# PROB_S7CAS_DAC.net
KiCad netlist of a schematic drawn in Altium Designer
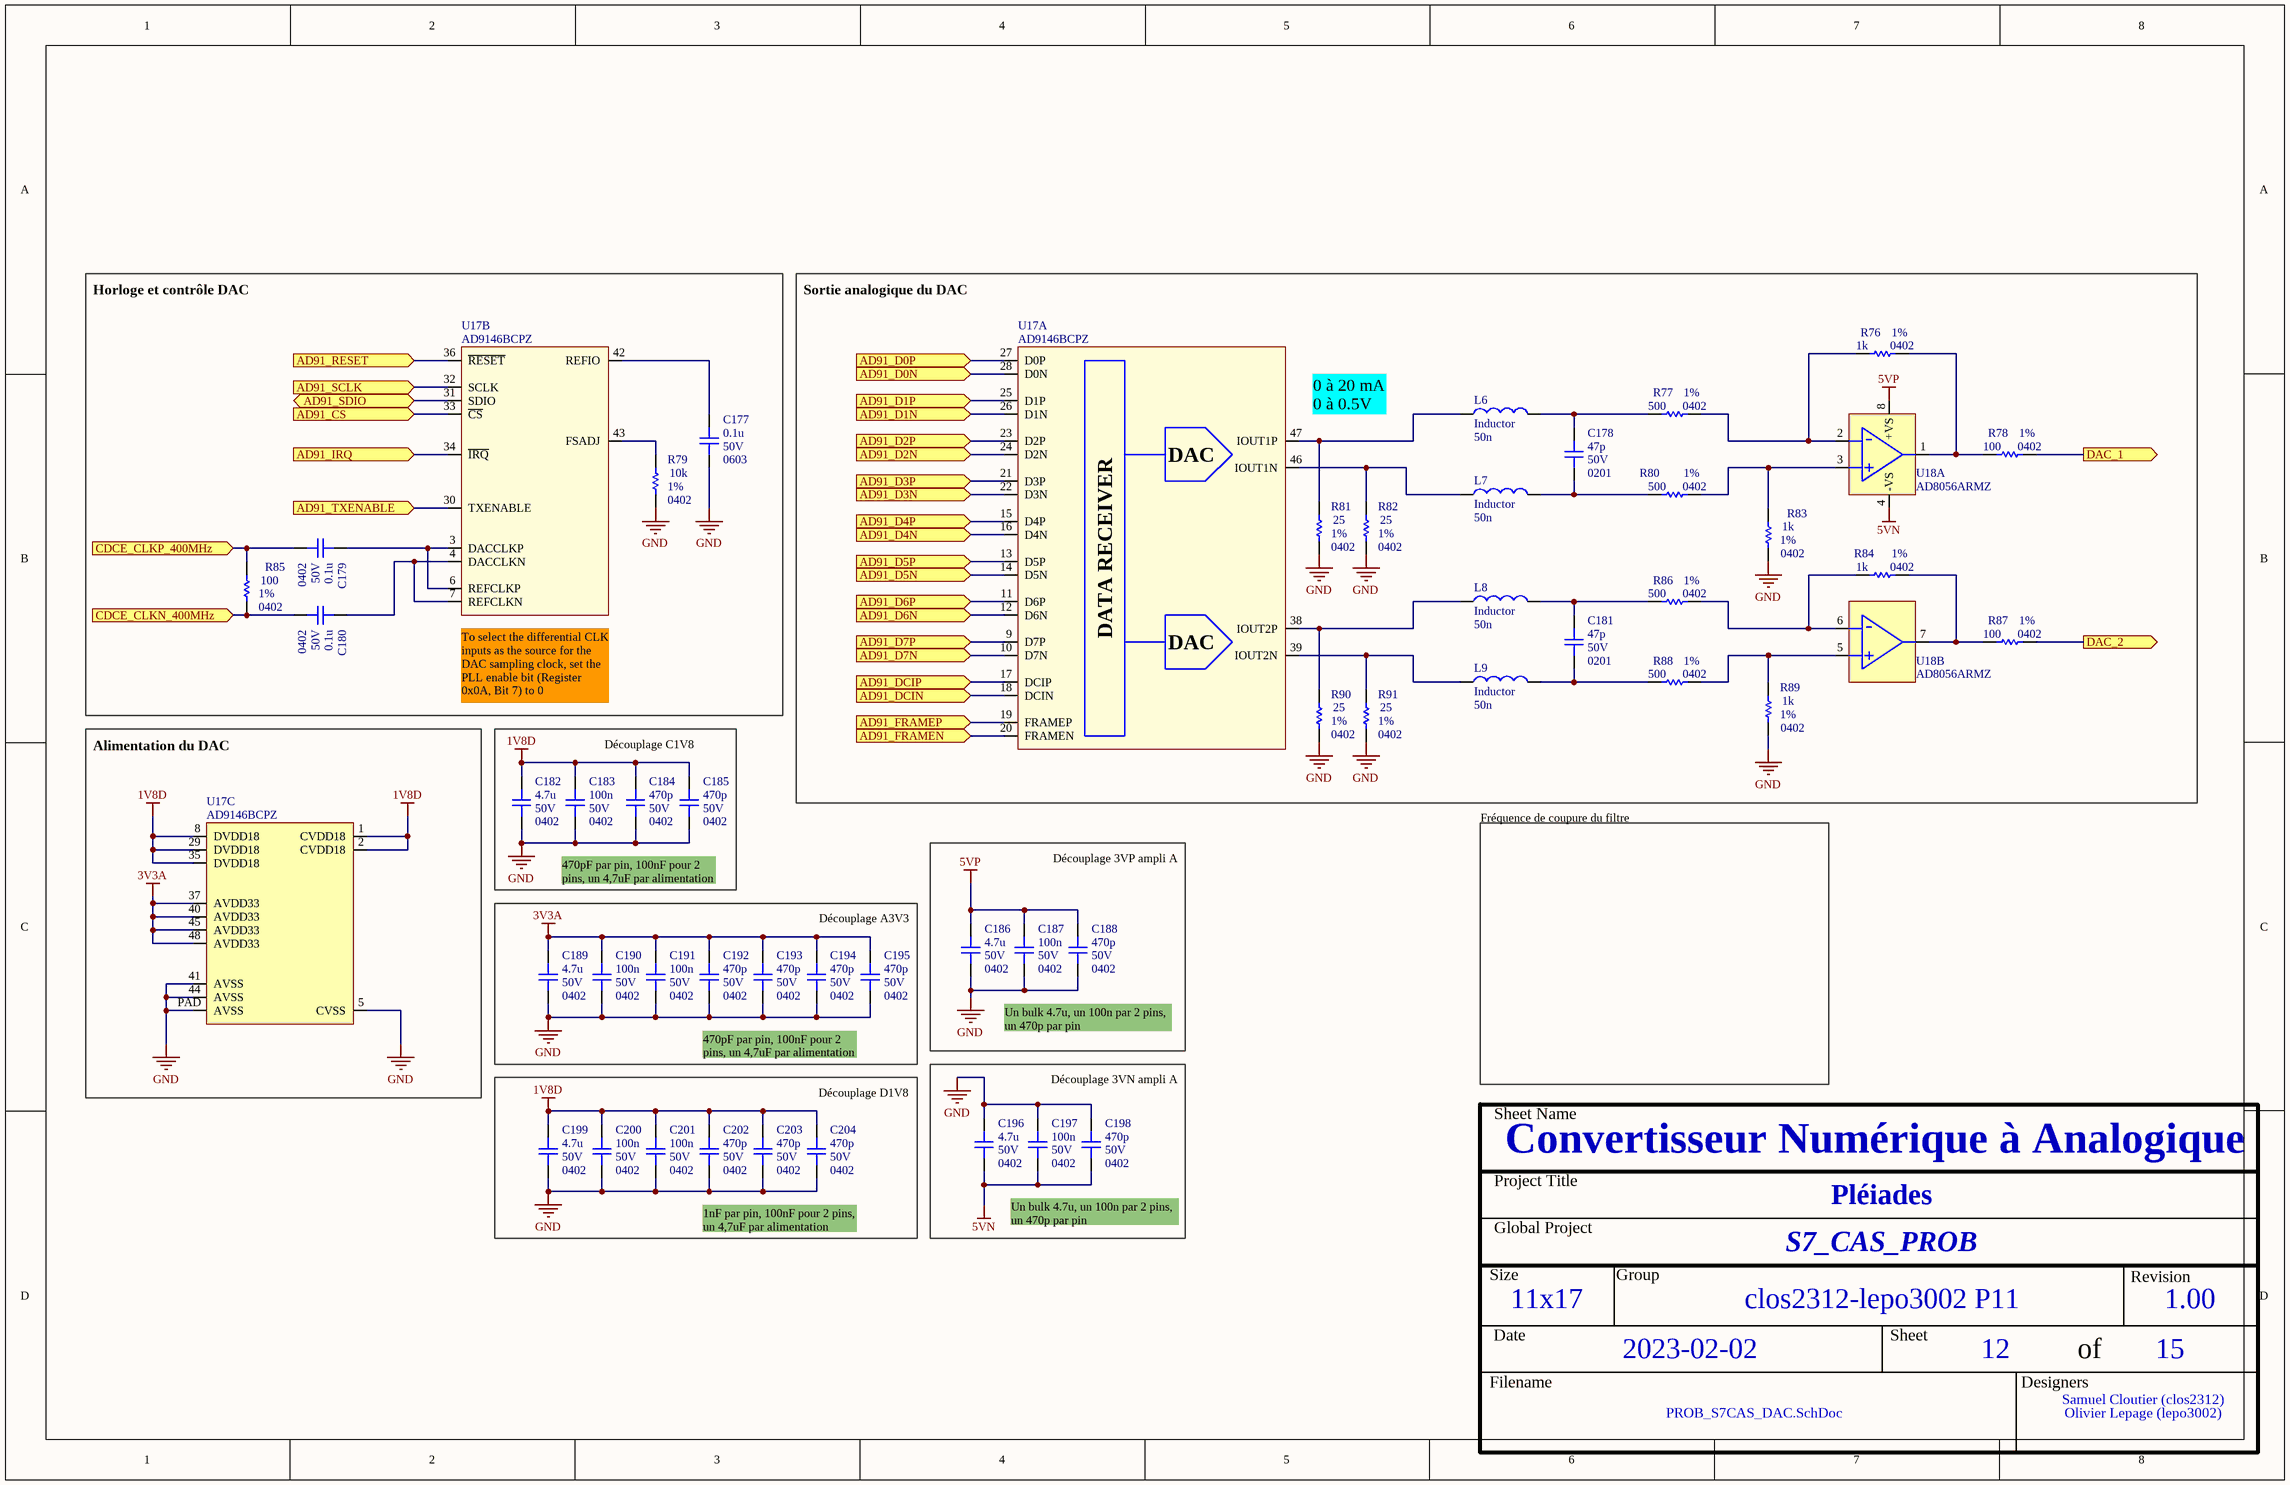
[diagram p0: PROB_S7CAS_DAC.SchDoc]

(export (version "E")
  (design (tool "Eeschema 10.0.6"))
  (components
    (comp (ref "C177")
      (value "0.1u")
      (footprint "CAP_0603")
      (description "CAP - 0603")
      (fields
        (field (name "VOLTAGE") "50V")
        (field (name "PACKAGE") "0603")
        (field (name "CREATEDBY") "Jonathan Bouchard")
      )
      (libsource (lib "S7CAS_LIB2021") (part "CAP - 0603"))
    )
    (comp (ref "C178")
      (value "47p")
      (footprint "CAP_0201")
      (description "CAP - 0201")
      (fields
        (field (name "VOLTAGE") "50V")
        (field (name "PACKAGE") "0201")
        (field (name "CREATEDBY") "Jonathan Bouchard")
      )
      (libsource (lib "S7CAS_LIB2021") (part "CAP - 0201"))
    )
    (comp (ref "C179")
      (value "0.1u")
      (footprint "CAP_0402")
      (description "CAP - 0402")
      (fields
        (field (name "VOLTAGE") "50V")
        (field (name "PACKAGE") "0402")
        (field (name "CREATEDBY") "Jonathan Bouchard")
      )
      (libsource (lib "S7CAS_LIB2021") (part "CAP - 0402"))
    )
    (comp (ref "C180")
      (value "0.1u")
      (footprint "CAP_0402")
      (description "CAP - 0402")
      (fields
        (field (name "VOLTAGE") "50V")
        (field (name "PACKAGE") "0402")
        (field (name "CREATEDBY") "Jonathan Bouchard")
      )
      (libsource (lib "S7CAS_LIB2021") (part "CAP - 0402"))
    )
    (comp (ref "C181")
      (value "47p")
      (footprint "CAP_0201")
      (description "CAP - 0201")
      (fields
        (field (name "VOLTAGE") "50V")
        (field (name "PACKAGE") "0201")
        (field (name "CREATEDBY") "Jonathan Bouchard")
      )
      (libsource (lib "S7CAS_LIB2021") (part "CAP - 0201"))
    )
    (comp (ref "C182")
      (value "4.7u")
      (footprint "CAP_0402")
      (description "CAP - 0402")
      (fields
        (field (name "VOLTAGE") "50V")
        (field (name "PACKAGE") "0402")
        (field (name "CREATEDBY") "Jonathan Bouchard")
      )
      (libsource (lib "S7CAS_LIB2021") (part "CAP - 0402"))
    )
    (comp (ref "C183")
      (value "100n")
      (footprint "CAP_0402")
      (description "CAP - 0402")
      (fields
        (field (name "VOLTAGE") "50V")
        (field (name "PACKAGE") "0402")
        (field (name "CREATEDBY") "Jonathan Bouchard")
      )
      (libsource (lib "S7CAS_LIB2021") (part "CAP - 0402"))
    )
    (comp (ref "C184")
      (value "470p")
      (footprint "CAP_0402")
      (description "CAP - 0402")
      (fields
        (field (name "VOLTAGE") "50V")
        (field (name "PACKAGE") "0402")
        (field (name "CREATEDBY") "Jonathan Bouchard")
      )
      (libsource (lib "S7CAS_LIB2021") (part "CAP - 0402"))
    )
    (comp (ref "C185")
      (value "470p")
      (footprint "CAP_0402")
      (description "CAP - 0402")
      (fields
        (field (name "VOLTAGE") "50V")
        (field (name "PACKAGE") "0402")
        (field (name "CREATEDBY") "Jonathan Bouchard")
      )
      (libsource (lib "S7CAS_LIB2021") (part "CAP - 0402"))
    )
    (comp (ref "C186")
      (value "4.7u")
      (footprint "CAP_0402")
      (description "CAP - 0402")
      (fields
        (field (name "VOLTAGE") "50V")
        (field (name "PACKAGE") "0402")
        (field (name "CREATEDBY") "Jonathan Bouchard")
      )
      (libsource (lib "S7CAS_LIB2021") (part "CAP - 0402"))
    )
    (comp (ref "C187")
      (value "100n")
      (footprint "CAP_0402")
      (description "CAP - 0402")
      (fields
        (field (name "VOLTAGE") "50V")
        (field (name "PACKAGE") "0402")
        (field (name "CREATEDBY") "Jonathan Bouchard")
      )
      (libsource (lib "S7CAS_LIB2021") (part "CAP - 0402"))
    )
    (comp (ref "C188")
      (value "470p")
      (footprint "CAP_0402")
      (description "CAP - 0402")
      (fields
        (field (name "VOLTAGE") "50V")
        (field (name "PACKAGE") "0402")
        (field (name "CREATEDBY") "Jonathan Bouchard")
      )
      (libsource (lib "S7CAS_LIB2021") (part "CAP - 0402"))
    )
    (comp (ref "C189")
      (value "4.7u")
      (footprint "CAP_0402")
      (description "CAP - 0402")
      (fields
        (field (name "VOLTAGE") "50V")
        (field (name "PACKAGE") "0402")
        (field (name "CREATEDBY") "Jonathan Bouchard")
      )
      (libsource (lib "S7CAS_LIB2021") (part "CAP - 0402"))
    )
    (comp (ref "C190")
      (value "100n")
      (footprint "CAP_0402")
      (description "CAP - 0402")
      (fields
        (field (name "VOLTAGE") "50V")
        (field (name "PACKAGE") "0402")
        (field (name "CREATEDBY") "Jonathan Bouchard")
      )
      (libsource (lib "S7CAS_LIB2021") (part "CAP - 0402"))
    )
    (comp (ref "C191")
      (value "100n")
      (footprint "CAP_0402")
      (description "CAP - 0402")
      (fields
        (field (name "VOLTAGE") "50V")
        (field (name "PACKAGE") "0402")
        (field (name "CREATEDBY") "Jonathan Bouchard")
      )
      (libsource (lib "S7CAS_LIB2021") (part "CAP - 0402"))
    )
    (comp (ref "C192")
      (value "470p")
      (footprint "CAP_0402")
      (description "CAP - 0402")
      (fields
        (field (name "VOLTAGE") "50V")
        (field (name "PACKAGE") "0402")
        (field (name "CREATEDBY") "Jonathan Bouchard")
      )
      (libsource (lib "S7CAS_LIB2021") (part "CAP - 0402"))
    )
    (comp (ref "C193")
      (value "470p")
      (footprint "CAP_0402")
      (description "CAP - 0402")
      (fields
        (field (name "VOLTAGE") "50V")
        (field (name "PACKAGE") "0402")
        (field (name "CREATEDBY") "Jonathan Bouchard")
      )
      (libsource (lib "S7CAS_LIB2021") (part "CAP - 0402"))
    )
    (comp (ref "C194")
      (value "470p")
      (footprint "CAP_0402")
      (description "CAP - 0402")
      (fields
        (field (name "VOLTAGE") "50V")
        (field (name "PACKAGE") "0402")
        (field (name "CREATEDBY") "Jonathan Bouchard")
      )
      (libsource (lib "S7CAS_LIB2021") (part "CAP - 0402"))
    )
    (comp (ref "C195")
      (value "470p")
      (footprint "CAP_0402")
      (description "CAP - 0402")
      (fields
        (field (name "VOLTAGE") "50V")
        (field (name "PACKAGE") "0402")
        (field (name "CREATEDBY") "Jonathan Bouchard")
      )
      (libsource (lib "S7CAS_LIB2021") (part "CAP - 0402"))
    )
    (comp (ref "C196")
      (value "4.7u")
      (footprint "CAP_0402")
      (description "CAP - 0402")
      (fields
        (field (name "VOLTAGE") "50V")
        (field (name "PACKAGE") "0402")
        (field (name "CREATEDBY") "Jonathan Bouchard")
      )
      (libsource (lib "S7CAS_LIB2021") (part "CAP - 0402"))
    )
    (comp (ref "C197")
      (value "100n")
      (footprint "CAP_0402")
      (description "CAP - 0402")
      (fields
        (field (name "VOLTAGE") "50V")
        (field (name "PACKAGE") "0402")
        (field (name "CREATEDBY") "Jonathan Bouchard")
      )
      (libsource (lib "S7CAS_LIB2021") (part "CAP - 0402"))
    )
    (comp (ref "C198")
      (value "470p")
      (footprint "CAP_0402")
      (description "CAP - 0402")
      (fields
        (field (name "VOLTAGE") "50V")
        (field (name "PACKAGE") "0402")
        (field (name "CREATEDBY") "Jonathan Bouchard")
      )
      (libsource (lib "S7CAS_LIB2021") (part "CAP - 0402"))
    )
    (comp (ref "C199")
      (value "4.7u")
      (footprint "CAP_0402")
      (description "CAP - 0402")
      (fields
        (field (name "VOLTAGE") "50V")
        (field (name "PACKAGE") "0402")
        (field (name "CREATEDBY") "Jonathan Bouchard")
      )
      (libsource (lib "S7CAS_LIB2021") (part "CAP - 0402"))
    )
    (comp (ref "C200")
      (value "100n")
      (footprint "CAP_0402")
      (description "CAP - 0402")
      (fields
        (field (name "VOLTAGE") "50V")
        (field (name "PACKAGE") "0402")
        (field (name "CREATEDBY") "Jonathan Bouchard")
      )
      (libsource (lib "S7CAS_LIB2021") (part "CAP - 0402"))
    )
    (comp (ref "C201")
      (value "100n")
      (footprint "CAP_0402")
      (description "CAP - 0402")
      (fields
        (field (name "VOLTAGE") "50V")
        (field (name "PACKAGE") "0402")
        (field (name "CREATEDBY") "Jonathan Bouchard")
      )
      (libsource (lib "S7CAS_LIB2021") (part "CAP - 0402"))
    )
    (comp (ref "C202")
      (value "470p")
      (footprint "CAP_0402")
      (description "CAP - 0402")
      (fields
        (field (name "VOLTAGE") "50V")
        (field (name "PACKAGE") "0402")
        (field (name "CREATEDBY") "Jonathan Bouchard")
      )
      (libsource (lib "S7CAS_LIB2021") (part "CAP - 0402"))
    )
    (comp (ref "C203")
      (value "470p")
      (footprint "CAP_0402")
      (description "CAP - 0402")
      (fields
        (field (name "VOLTAGE") "50V")
        (field (name "PACKAGE") "0402")
        (field (name "CREATEDBY") "Jonathan Bouchard")
      )
      (libsource (lib "S7CAS_LIB2021") (part "CAP - 0402"))
    )
    (comp (ref "C204")
      (value "470p")
      (footprint "CAP_0402")
      (description "CAP - 0402")
      (fields
        (field (name "VOLTAGE") "50V")
        (field (name "PACKAGE") "0402")
        (field (name "CREATEDBY") "Jonathan Bouchard")
      )
      (libsource (lib "S7CAS_LIB2021") (part "CAP - 0402"))
    )
    (comp (ref "L6")
      (value "Inductor")
      (footprint "INDM5250X66N")
      (description "IND PWR BEAD 50NH 48A SMD")
      (fields (field (name "ALTIUM_VALUE") "50n"))
      (libsource (lib "LIB_TEMP_S7CAS_SCH") (part "Inductor"))
    )
    (comp (ref "L7")
      (value "Inductor")
      (footprint "INDM5250X66N")
      (description "IND PWR BEAD 50NH 48A SMD")
      (fields (field (name "ALTIUM_VALUE") "50n"))
      (libsource (lib "LIB_TEMP_S7CAS_SCH") (part "Inductor"))
    )
    (comp (ref "L8")
      (value "Inductor")
      (footprint "INDM5250X66N")
      (description "IND PWR BEAD 50NH 48A SMD")
      (fields (field (name "ALTIUM_VALUE") "50n"))
      (libsource (lib "LIB_TEMP_S7CAS_SCH") (part "Inductor"))
    )
    (comp (ref "L9")
      (value "Inductor")
      (footprint "INDM5250X66N")
      (description "IND PWR BEAD 50NH 48A SMD")
      (fields (field (name "ALTIUM_VALUE") "50n"))
      (libsource (lib "LIB_TEMP_S7CAS_SCH") (part "Inductor"))
    )
    (comp (ref "R76")
      (value "1k")
      (footprint "RES_0402")
      (description "RES - 0402")
      (fields
        (field (name "VOLTAGE") "50V")
        (field (name "POWER") "1/16W")
        (field (name "PACKAGE") "0402")
        (field (name "PRECISION") "1%")
        (field (name "CREATEDBY") "Jonathan Bouchard")
      )
      (libsource (lib "S7CAS_LIB2021") (part "RES - 0402"))
    )
    (comp (ref "R77")
      (value "500")
      (footprint "RES_0402")
      (description "RES - 0402")
      (fields
        (field (name "VOLTAGE") "50V")
        (field (name "POWER") "1/16W")
        (field (name "PACKAGE") "0402")
        (field (name "PRECISION") "1%")
        (field (name "CREATEDBY") "Jonathan Bouchard")
      )
      (libsource (lib "S7CAS_LIB2021") (part "RES - 0402"))
    )
    (comp (ref "R78")
      (value "100")
      (footprint "RES_0402")
      (description "RES - 0402")
      (fields
        (field (name "VOLTAGE") "50V")
        (field (name "POWER") "1/16W")
        (field (name "PACKAGE") "0402")
        (field (name "PRECISION") "1%")
        (field (name "CREATEDBY") "Jonathan Bouchard")
      )
      (libsource (lib "S7CAS_LIB2021") (part "RES - 0402"))
    )
    (comp (ref "R79")
      (value "10k")
      (footprint "RES_0402")
      (description "RES - 0402")
      (fields
        (field (name "VOLTAGE") "50V")
        (field (name "POWER") "1/16W")
        (field (name "PACKAGE") "0402")
        (field (name "PRECISION") "1%")
        (field (name "CREATEDBY") "Jonathan Bouchard")
      )
      (libsource (lib "S7CAS_LIB2021") (part "RES - 0402"))
    )
    (comp (ref "R80")
      (value "500")
      (footprint "RES_0402")
      (description "RES - 0402")
      (fields
        (field (name "VOLTAGE") "50V")
        (field (name "POWER") "1/16W")
        (field (name "PACKAGE") "0402")
        (field (name "PRECISION") "1%")
        (field (name "CREATEDBY") "Jonathan Bouchard")
      )
      (libsource (lib "S7CAS_LIB2021") (part "RES - 0402"))
    )
    (comp (ref "R81")
      (value "25")
      (footprint "RES_0402")
      (description "RES - 0402")
      (fields
        (field (name "VOLTAGE") "50V")
        (field (name "POWER") "1/16W")
        (field (name "PACKAGE") "0402")
        (field (name "PRECISION") "1%")
        (field (name "CREATEDBY") "Jonathan Bouchard")
      )
      (libsource (lib "S7CAS_LIB2021") (part "RES - 0402"))
    )
    (comp (ref "R82")
      (value "25")
      (footprint "RES_0402")
      (description "RES - 0402")
      (fields
        (field (name "VOLTAGE") "50V")
        (field (name "POWER") "1/16W")
        (field (name "PACKAGE") "0402")
        (field (name "PRECISION") "1%")
        (field (name "CREATEDBY") "Jonathan Bouchard")
      )
      (libsource (lib "S7CAS_LIB2021") (part "RES - 0402"))
    )
    (comp (ref "R83")
      (value "1k")
      (footprint "RES_0402")
      (description "RES - 0402")
      (fields
        (field (name "VOLTAGE") "50V")
        (field (name "POWER") "1/16W")
        (field (name "PACKAGE") "0402")
        (field (name "PRECISION") "1%")
        (field (name "CREATEDBY") "Jonathan Bouchard")
      )
      (libsource (lib "S7CAS_LIB2021") (part "RES - 0402"))
    )
    (comp (ref "R84")
      (value "1k")
      (footprint "RES_0402")
      (description "RES - 0402")
      (fields
        (field (name "VOLTAGE") "50V")
        (field (name "POWER") "1/16W")
        (field (name "PACKAGE") "0402")
        (field (name "PRECISION") "1%")
        (field (name "CREATEDBY") "Jonathan Bouchard")
      )
      (libsource (lib "S7CAS_LIB2021") (part "RES - 0402"))
    )
    (comp (ref "R85")
      (value "100")
      (footprint "RES_0402")
      (description "RES - 0402")
      (fields
        (field (name "VOLTAGE") "50V")
        (field (name "POWER") "1/16W")
        (field (name "PACKAGE") "0402")
        (field (name "PRECISION") "1%")
        (field (name "CREATEDBY") "Jonathan Bouchard")
      )
      (libsource (lib "S7CAS_LIB2021") (part "RES - 0402"))
    )
    (comp (ref "R86")
      (value "500")
      (footprint "RES_0402")
      (description "RES - 0402")
      (fields
        (field (name "VOLTAGE") "50V")
        (field (name "POWER") "1/16W")
        (field (name "PACKAGE") "0402")
        (field (name "PRECISION") "1%")
        (field (name "CREATEDBY") "Jonathan Bouchard")
      )
      (libsource (lib "S7CAS_LIB2021") (part "RES - 0402"))
    )
    (comp (ref "R87")
      (value "100")
      (footprint "RES_0402")
      (description "RES - 0402")
      (fields
        (field (name "VOLTAGE") "50V")
        (field (name "POWER") "1/16W")
        (field (name "PACKAGE") "0402")
        (field (name "PRECISION") "1%")
        (field (name "CREATEDBY") "Jonathan Bouchard")
      )
      (libsource (lib "S7CAS_LIB2021") (part "RES - 0402"))
    )
    (comp (ref "R88")
      (value "500")
      (footprint "RES_0402")
      (description "RES - 0402")
      (fields
        (field (name "VOLTAGE") "50V")
        (field (name "POWER") "1/16W")
        (field (name "PACKAGE") "0402")
        (field (name "PRECISION") "1%")
        (field (name "CREATEDBY") "Jonathan Bouchard")
      )
      (libsource (lib "S7CAS_LIB2021") (part "RES - 0402"))
    )
    (comp (ref "R89")
      (value "1k")
      (footprint "RES_0402")
      (description "RES - 0402")
      (fields
        (field (name "VOLTAGE") "50V")
        (field (name "POWER") "1/16W")
        (field (name "PACKAGE") "0402")
        (field (name "PRECISION") "1%")
        (field (name "CREATEDBY") "Jonathan Bouchard")
      )
      (libsource (lib "S7CAS_LIB2021") (part "RES - 0402"))
    )
    (comp (ref "R90")
      (value "25")
      (footprint "RES_0402")
      (description "RES - 0402")
      (fields
        (field (name "VOLTAGE") "50V")
        (field (name "POWER") "1/16W")
        (field (name "PACKAGE") "0402")
        (field (name "PRECISION") "1%")
        (field (name "CREATEDBY") "Jonathan Bouchard")
      )
      (libsource (lib "S7CAS_LIB2021") (part "RES - 0402"))
    )
    (comp (ref "R91")
      (value "25")
      (footprint "RES_0402")
      (description "RES - 0402")
      (fields
        (field (name "VOLTAGE") "50V")
        (field (name "POWER") "1/16W")
        (field (name "PACKAGE") "0402")
        (field (name "PRECISION") "1%")
        (field (name "CREATEDBY") "Jonathan Bouchard")
      )
      (libsource (lib "S7CAS_LIB2021") (part "RES - 0402"))
    )
    (comp (ref "U17")
      (value "AD9146BCPZ")
      (footprint "DAC_AD9146BCPZ")
      (description "DAC - 16BIT SRL HIGH SPEED - QFN-48")
      (fields
        (field (name "VOLTAGE") "3.13 V ~ 3.47 V / 1.71 V ~ 1.89 V")
        (field (name "MFG") "Analog Devices Inc.")
        (field (name "CREATEDBY") "Jonathan Bouchard")
      )
      (libsource (lib "S7CAS_LIB2021") (part "DAC_AD9146BCPZ"))
    )
    (comp (ref "U18")
      (value "AD8056ARMZ")
      (footprint "OPAMP_AD8056ARMZ")
      (description "OPAMP - VFB 300MHZ - 8MSOP")
      (fields
        (field (name "VOLTAGE") "8 V ~ 12 V, ±4 V ~ 6 V")
        (field (name "MFG") "Analog Devices")
        (field (name "CREATEDBY") "Jonathan Bouchard")
      )
      (libsource (lib "S7CAS_LIB2021") (part "OPAMP_AD8056ARMZ"))
    )
  )
  (nets
    (net (code "1") (name "/AD91_CS") (class "Default")
      (node (ref "U17") (pin "33") (pinfunction "~{CS}_33") (pintype "passive"))
    )
    (net (code "2") (name "/AD91_D0N") (class "Default")
      (node (ref "U17") (pin "28") (pinfunction "D0N_28") (pintype "passive"))
    )
    (net (code "3") (name "/AD91_D0P") (class "Default")
      (node (ref "U17") (pin "27") (pinfunction "D0P_27") (pintype "passive"))
    )
    (net (code "4") (name "/AD91_D1N") (class "Default")
      (node (ref "U17") (pin "26") (pinfunction "D1N_26") (pintype "passive"))
    )
    (net (code "5") (name "/AD91_D1P") (class "Default")
      (node (ref "U17") (pin "25") (pinfunction "D1P_25") (pintype "passive"))
    )
    (net (code "6") (name "/AD91_D2N") (class "Default")
      (node (ref "U17") (pin "24") (pinfunction "D2N_24") (pintype "passive"))
    )
    (net (code "7") (name "/AD91_D2P") (class "Default")
      (node (ref "U17") (pin "23") (pinfunction "D2P_23") (pintype "passive"))
    )
    (net (code "8") (name "/AD91_D3N") (class "Default")
      (node (ref "U17") (pin "22") (pinfunction "D3N_22") (pintype "passive"))
    )
    (net (code "9") (name "/AD91_D3P") (class "Default")
      (node (ref "U17") (pin "21") (pinfunction "D3P_21") (pintype "passive"))
    )
    (net (code "10") (name "/AD91_D4N") (class "Default")
      (node (ref "U17") (pin "16") (pinfunction "D4N_16") (pintype "passive"))
    )
    (net (code "11") (name "/AD91_D4P") (class "Default")
      (node (ref "U17") (pin "15") (pinfunction "D4P_15") (pintype "passive"))
    )
    (net (code "12") (name "/AD91_D5N") (class "Default")
      (node (ref "U17") (pin "14") (pinfunction "D5N_14") (pintype "passive"))
    )
    (net (code "13") (name "/AD91_D5P") (class "Default")
      (node (ref "U17") (pin "13") (pinfunction "D5P_13") (pintype "passive"))
    )
    (net (code "14") (name "/AD91_D6N") (class "Default")
      (node (ref "U17") (pin "12") (pinfunction "D6N_12") (pintype "passive"))
    )
    (net (code "15") (name "/AD91_D6P") (class "Default")
      (node (ref "U17") (pin "11") (pinfunction "D6P_11") (pintype "passive"))
    )
    (net (code "16") (name "/AD91_D7N") (class "Default")
      (node (ref "U17") (pin "10") (pinfunction "D7N_10") (pintype "passive"))
    )
    (net (code "17") (name "/AD91_D7P") (class "Default")
      (node (ref "U17") (pin "9") (pinfunction "D7P_9") (pintype "passive"))
    )
    (net (code "18") (name "/AD91_DCIN") (class "Default")
      (node (ref "U17") (pin "18") (pinfunction "DCIN_18") (pintype "passive"))
    )
    (net (code "19") (name "/AD91_DCIP") (class "Default")
      (node (ref "U17") (pin "17") (pinfunction "DCIP_17") (pintype "passive"))
    )
    (net (code "20") (name "/AD91_FRAMEN") (class "Default")
      (node (ref "U17") (pin "20") (pinfunction "FRAMEN_20") (pintype "passive"))
    )
    (net (code "21") (name "/AD91_FRAMEP") (class "Default")
      (node (ref "U17") (pin "19") (pinfunction "FRAMEP_19") (pintype "passive"))
    )
    (net (code "22") (name "/AD91_IRQ") (class "Default")
      (node (ref "U17") (pin "34") (pinfunction "~{IRQ}_34") (pintype "passive"))
    )
    (net (code "23") (name "/AD91_RESET") (class "Default")
      (node (ref "U17") (pin "36") (pinfunction "~{RESET}_36") (pintype "passive"))
    )
    (net (code "24") (name "/AD91_SCLK") (class "Default")
      (node (ref "U17") (pin "32") (pinfunction "SCLK_32") (pintype "passive"))
    )
    (net (code "25") (name "/AD91_SDIO") (class "Default")
      (node (ref "U17") (pin "31") (pinfunction "SDIO_31") (pintype "passive"))
    )
    (net (code "26") (name "/AD91_TXENABLE") (class "Default")
      (node (ref "U17") (pin "30") (pinfunction "TXENABLE_30") (pintype "passive"))
    )
    (net (code "27") (name "/CDCE_CLKN_400MHz") (class "Default")
      (node (ref "C180") (pin "1") (pinfunction "1_1") (pintype "passive"))
      (node (ref "R85") (pin "1") (pinfunction "1_1") (pintype "passive"))
    )
    (net (code "28") (name "/CDCE_CLKP_400MHz") (class "Default")
      (node (ref "C179") (pin "1") (pinfunction "1_1") (pintype "passive"))
      (node (ref "R85") (pin "2") (pinfunction "2_2") (pintype "passive"))
    )
    (net (code "29") (name "/DAC_1") (class "Default")
      (node (ref "R78") (pin "2") (pinfunction "2_2") (pintype "passive"))
    )
    (net (code "30") (name "/DAC_2") (class "Default")
      (node (ref "R87") (pin "2") (pinfunction "2_2") (pintype "passive"))
    )
    (net (code "31") (name "1V8D") (class "Default")
      (node (ref "C182") (pin "2") (pinfunction "2_2") (pintype "passive"))
      (node (ref "C183") (pin "2") (pinfunction "2_2") (pintype "passive"))
      (node (ref "C184") (pin "2") (pinfunction "2_2") (pintype "passive"))
      (node (ref "C185") (pin "2") (pinfunction "2_2") (pintype "passive"))
      (node (ref "C199") (pin "2") (pinfunction "2_2") (pintype "passive"))
      (node (ref "C200") (pin "2") (pinfunction "2_2") (pintype "passive"))
      (node (ref "C201") (pin "2") (pinfunction "2_2") (pintype "passive"))
      (node (ref "C202") (pin "2") (pinfunction "2_2") (pintype "passive"))
      (node (ref "C203") (pin "2") (pinfunction "2_2") (pintype "passive"))
      (node (ref "C204") (pin "2") (pinfunction "2_2") (pintype "passive"))
      (node (ref "U17") (pin "1") (pinfunction "CVDD18_1") (pintype "passive"))
      (node (ref "U17") (pin "2") (pinfunction "CVDD18_2") (pintype "passive"))
      (node (ref "U17") (pin "29") (pinfunction "DVDD18_29") (pintype "passive"))
      (node (ref "U17") (pin "35") (pinfunction "DVDD18_35") (pintype "passive"))
      (node (ref "U17") (pin "8") (pinfunction "DVDD18_8") (pintype "passive"))
    )
    (net (code "32") (name "3V3A") (class "Default")
      (node (ref "C189") (pin "2") (pinfunction "2_2") (pintype "passive"))
      (node (ref "C190") (pin "2") (pinfunction "2_2") (pintype "passive"))
      (node (ref "C191") (pin "2") (pinfunction "2_2") (pintype "passive"))
      (node (ref "C192") (pin "2") (pinfunction "2_2") (pintype "passive"))
      (node (ref "C193") (pin "2") (pinfunction "2_2") (pintype "passive"))
      (node (ref "C194") (pin "2") (pinfunction "2_2") (pintype "passive"))
      (node (ref "C195") (pin "2") (pinfunction "2_2") (pintype "passive"))
      (node (ref "U17") (pin "37") (pinfunction "AVDD33_37") (pintype "passive"))
      (node (ref "U17") (pin "40") (pinfunction "AVDD33_40") (pintype "passive"))
      (node (ref "U17") (pin "45") (pinfunction "AVDD33_45") (pintype "passive"))
      (node (ref "U17") (pin "48") (pinfunction "AVDD33_48") (pintype "passive"))
    )
    (net (code "33") (name "5VN") (class "Default")
      (node (ref "C196") (pin "1") (pinfunction "1_1") (pintype "passive"))
      (node (ref "C197") (pin "1") (pinfunction "1_1") (pintype "passive"))
      (node (ref "C198") (pin "1") (pinfunction "1_1") (pintype "passive"))
      (node (ref "U18") (pin "4") (pinfunction "-VS_4") (pintype "passive"))
    )
    (net (code "34") (name "5VP") (class "Default")
      (node (ref "C186") (pin "2") (pinfunction "2_2") (pintype "passive"))
      (node (ref "C187") (pin "2") (pinfunction "2_2") (pintype "passive"))
      (node (ref "C188") (pin "2") (pinfunction "2_2") (pintype "passive"))
      (node (ref "U18") (pin "8") (pinfunction "+VS_8") (pintype "passive"))
    )
    (net (code "35") (name "GND") (class "Default")
      (node (ref "C177") (pin "1") (pinfunction "1_1") (pintype "passive"))
      (node (ref "C182") (pin "1") (pinfunction "1_1") (pintype "passive"))
      (node (ref "C183") (pin "1") (pinfunction "1_1") (pintype "passive"))
      (node (ref "C184") (pin "1") (pinfunction "1_1") (pintype "passive"))
      (node (ref "C185") (pin "1") (pinfunction "1_1") (pintype "passive"))
      (node (ref "C186") (pin "1") (pinfunction "1_1") (pintype "passive"))
      (node (ref "C187") (pin "1") (pinfunction "1_1") (pintype "passive"))
      (node (ref "C188") (pin "1") (pinfunction "1_1") (pintype "passive"))
      (node (ref "C189") (pin "1") (pinfunction "1_1") (pintype "passive"))
      (node (ref "C190") (pin "1") (pinfunction "1_1") (pintype "passive"))
      (node (ref "C191") (pin "1") (pinfunction "1_1") (pintype "passive"))
      (node (ref "C192") (pin "1") (pinfunction "1_1") (pintype "passive"))
      (node (ref "C193") (pin "1") (pinfunction "1_1") (pintype "passive"))
      (node (ref "C194") (pin "1") (pinfunction "1_1") (pintype "passive"))
      (node (ref "C195") (pin "1") (pinfunction "1_1") (pintype "passive"))
      (node (ref "C196") (pin "2") (pinfunction "2_2") (pintype "passive"))
      (node (ref "C197") (pin "2") (pinfunction "2_2") (pintype "passive"))
      (node (ref "C198") (pin "2") (pinfunction "2_2") (pintype "passive"))
      (node (ref "C199") (pin "1") (pinfunction "1_1") (pintype "passive"))
      (node (ref "C200") (pin "1") (pinfunction "1_1") (pintype "passive"))
      (node (ref "C201") (pin "1") (pinfunction "1_1") (pintype "passive"))
      (node (ref "C202") (pin "1") (pinfunction "1_1") (pintype "passive"))
      (node (ref "C203") (pin "1") (pinfunction "1_1") (pintype "passive"))
      (node (ref "C204") (pin "1") (pinfunction "1_1") (pintype "passive"))
      (node (ref "R79") (pin "1") (pinfunction "1_1") (pintype "passive"))
      (node (ref "R81") (pin "1") (pinfunction "1_1") (pintype "passive"))
      (node (ref "R82") (pin "1") (pinfunction "1_1") (pintype "passive"))
      (node (ref "R83") (pin "1") (pinfunction "1_1") (pintype "passive"))
      (node (ref "R89") (pin "1") (pinfunction "1_1") (pintype "passive"))
      (node (ref "R90") (pin "1") (pinfunction "1_1") (pintype "passive"))
      (node (ref "R91") (pin "1") (pinfunction "1_1") (pintype "passive"))
      (node (ref "U17") (pin "41") (pinfunction "AVSS_41") (pintype "passive"))
      (node (ref "U17") (pin "44") (pinfunction "AVSS_44") (pintype "passive"))
      (node (ref "U17") (pin "5") (pinfunction "CVSS_5") (pintype "passive"))
      (node (ref "U17") (pin "PAD") (pinfunction "AVSS_PAD") (pintype "passive"))
    )
    (net (code "36") (name "Net-(C178-Pad1)") (class "Default")
      (node (ref "C178") (pin "1") (pinfunction "1_1") (pintype "passive"))
      (node (ref "L7") (pin "2") (pinfunction "2_2") (pintype "passive"))
      (node (ref "R80") (pin "1") (pinfunction "1_1") (pintype "passive"))
    )
    (net (code "37") (name "Net-(C178-Pad2)") (class "Default")
      (node (ref "C178") (pin "2") (pinfunction "2_2") (pintype "passive"))
      (node (ref "L6") (pin "2") (pinfunction "2_2") (pintype "passive"))
      (node (ref "R77") (pin "1") (pinfunction "1_1") (pintype "passive"))
    )
    (net (code "38") (name "Net-(C181-Pad1)") (class "Default")
      (node (ref "C181") (pin "1") (pinfunction "1_1") (pintype "passive"))
      (node (ref "L9") (pin "2") (pinfunction "2_2") (pintype "passive"))
      (node (ref "R88") (pin "1") (pinfunction "1_1") (pintype "passive"))
    )
    (net (code "39") (name "Net-(C181-Pad2)") (class "Default")
      (node (ref "C181") (pin "2") (pinfunction "2_2") (pintype "passive"))
      (node (ref "L8") (pin "2") (pinfunction "2_2") (pintype "passive"))
      (node (ref "R86") (pin "1") (pinfunction "1_1") (pintype "passive"))
    )
    (net (code "40") (name "Net-(U17A-IOUT1N)") (class "Default")
      (node (ref "L7") (pin "1") (pinfunction "1_1") (pintype "passive"))
      (node (ref "R82") (pin "2") (pinfunction "2_2") (pintype "passive"))
      (node (ref "U17") (pin "46") (pinfunction "IOUT1N_46") (pintype "passive"))
    )
    (net (code "41") (name "Net-(U17A-IOUT1P)") (class "Default")
      (node (ref "L6") (pin "1") (pinfunction "1_1") (pintype "passive"))
      (node (ref "R81") (pin "2") (pinfunction "2_2") (pintype "passive"))
      (node (ref "U17") (pin "47") (pinfunction "IOUT1P_47") (pintype "passive"))
    )
    (net (code "42") (name "Net-(U17A-IOUT2N)") (class "Default")
      (node (ref "L9") (pin "1") (pinfunction "1_1") (pintype "passive"))
      (node (ref "R91") (pin "2") (pinfunction "2_2") (pintype "passive"))
      (node (ref "U17") (pin "39") (pinfunction "IOUT2N_39") (pintype "passive"))
    )
    (net (code "43") (name "Net-(U17A-IOUT2P)") (class "Default")
      (node (ref "L8") (pin "1") (pinfunction "1_1") (pintype "passive"))
      (node (ref "R90") (pin "2") (pinfunction "2_2") (pintype "passive"))
      (node (ref "U17") (pin "38") (pinfunction "IOUT2P_38") (pintype "passive"))
    )
    (net (code "44") (name "Net-(U17B-DACCLKN)") (class "Default")
      (node (ref "C180") (pin "2") (pinfunction "2_2") (pintype "passive"))
      (node (ref "U17") (pin "4") (pinfunction "DACCLKN_4") (pintype "passive"))
      (node (ref "U17") (pin "7") (pinfunction "REFCLKN_7") (pintype "passive"))
    )
    (net (code "45") (name "Net-(U17B-DACCLKP)") (class "Default")
      (node (ref "C179") (pin "2") (pinfunction "2_2") (pintype "passive"))
      (node (ref "U17") (pin "3") (pinfunction "DACCLKP_3") (pintype "passive"))
      (node (ref "U17") (pin "6") (pinfunction "REFCLKP_6") (pintype "passive"))
    )
    (net (code "46") (name "Net-(U17B-FSADJ)") (class "Default")
      (node (ref "R79") (pin "2") (pinfunction "2_2") (pintype "passive"))
      (node (ref "U17") (pin "43") (pinfunction "FSADJ_43") (pintype "passive"))
    )
    (net (code "47") (name "Net-(U17B-REFIO)") (class "Default")
      (node (ref "C177") (pin "2") (pinfunction "2_2") (pintype "passive"))
      (node (ref "U17") (pin "42") (pinfunction "REFIO_42") (pintype "passive"))
    )
    (net (code "48") (name "Net-(U18A-+IN1)") (class "Default")
      (node (ref "R80") (pin "2") (pinfunction "2_2") (pintype "passive"))
      (node (ref "R83") (pin "2") (pinfunction "2_2") (pintype "passive"))
      (node (ref "U18") (pin "3") (pinfunction "+IN1_3") (pintype "passive"))
    )
    (net (code "49") (name "Net-(U18A--IN1)") (class "Default")
      (node (ref "R76") (pin "1") (pinfunction "1_1") (pintype "passive"))
      (node (ref "R77") (pin "2") (pinfunction "2_2") (pintype "passive"))
      (node (ref "U18") (pin "2") (pinfunction "-IN1_2") (pintype "passive"))
    )
    (net (code "50") (name "Net-(U18A-OUT1)") (class "Default")
      (node (ref "R76") (pin "2") (pinfunction "2_2") (pintype "passive"))
      (node (ref "R78") (pin "1") (pinfunction "1_1") (pintype "passive"))
      (node (ref "U18") (pin "1") (pinfunction "OUT1_1") (pintype "passive"))
    )
    (net (code "51") (name "Net-(U18B-+IN2)") (class "Default")
      (node (ref "R88") (pin "2") (pinfunction "2_2") (pintype "passive"))
      (node (ref "R89") (pin "2") (pinfunction "2_2") (pintype "passive"))
      (node (ref "U18") (pin "5") (pinfunction "+IN2_5") (pintype "passive"))
    )
    (net (code "52") (name "Net-(U18B--IN2)") (class "Default")
      (node (ref "R84") (pin "1") (pinfunction "1_1") (pintype "passive"))
      (node (ref "R86") (pin "2") (pinfunction "2_2") (pintype "passive"))
      (node (ref "U18") (pin "6") (pinfunction "-IN2_6") (pintype "passive"))
    )
    (net (code "53") (name "Net-(U18B-OUT2)") (class "Default")
      (node (ref "R84") (pin "2") (pinfunction "2_2") (pintype "passive"))
      (node (ref "R87") (pin "1") (pinfunction "1_1") (pintype "passive"))
      (node (ref "U18") (pin "7") (pinfunction "OUT2_7") (pintype "passive"))
    )
  )
)
